# FliegerPCB10.net
KiCad netlist of a schematic drawn in EAGLE
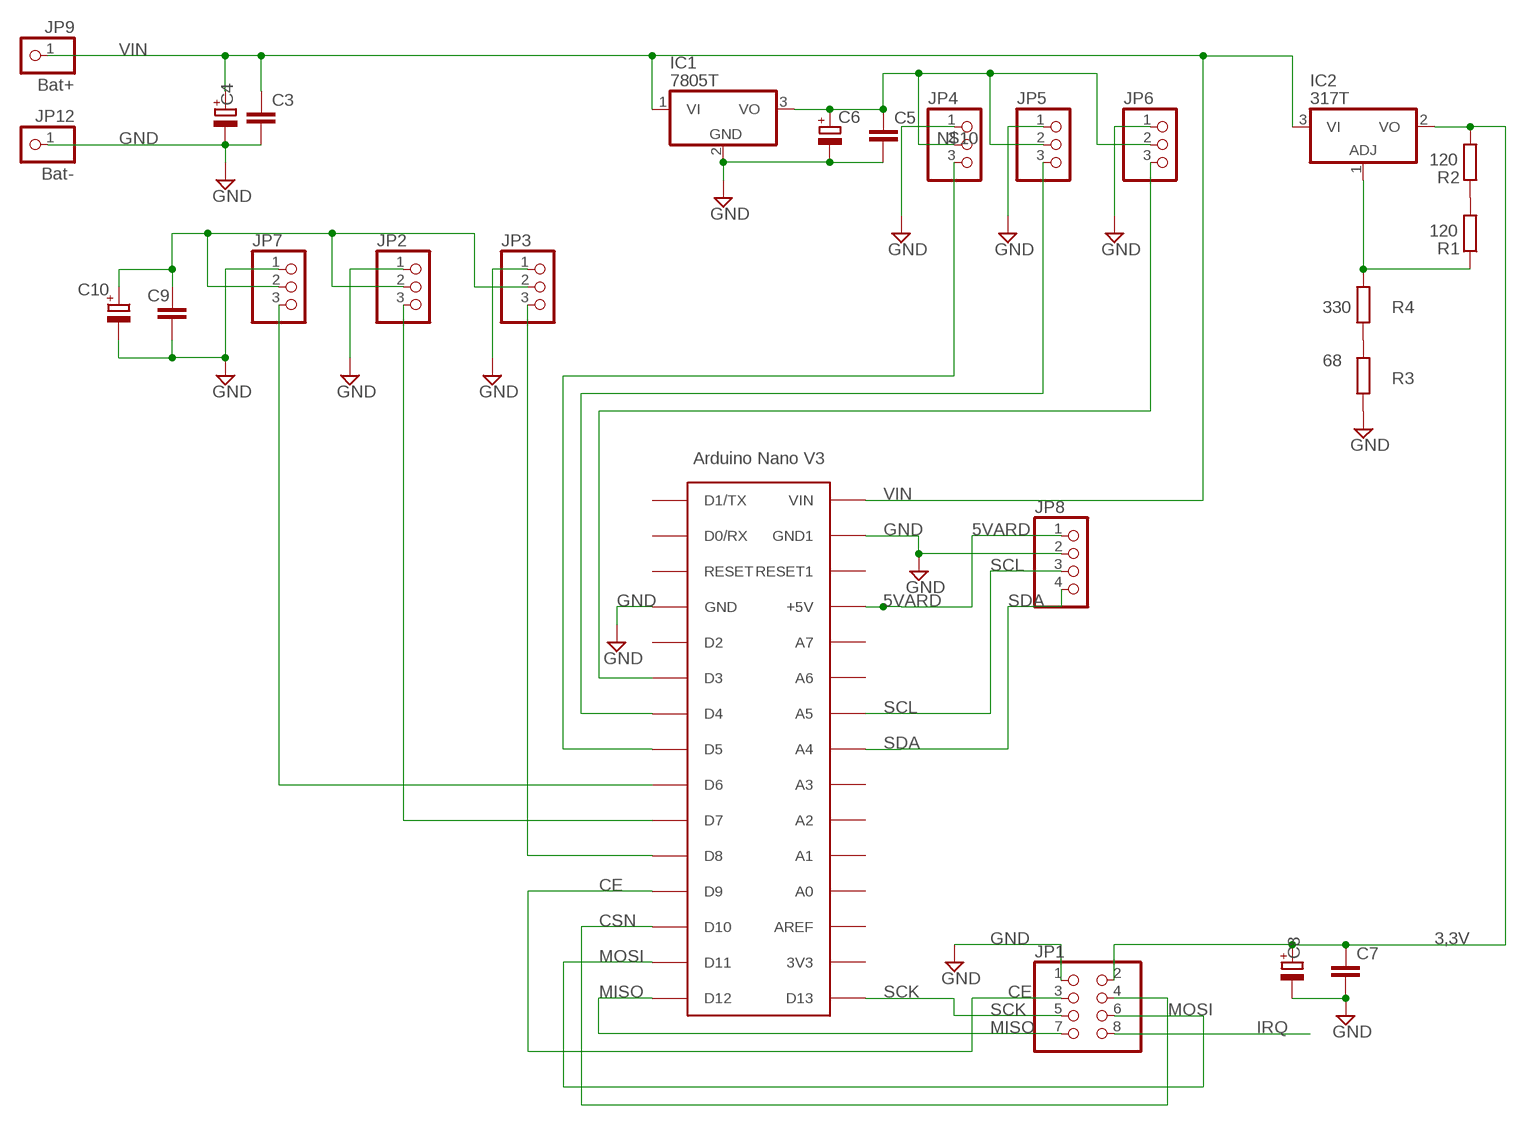
[diagram p0: schematic, sheet 1]

(export (version "E")
  (design (tool "Eeschema 10.0.6"))
  (components
    (comp (ref "C3")
      (value "C-EU050-024X044")
      (footprint "eagle-import:C050-024X044")
      (libsource (lib "eagle-import") (part "C-EU050-024X044"))
    )
    (comp (ref "C4")
      (value "CPOL-EUE5-10.5")
      (footprint "eagle-import:E5-10,5")
      (libsource (lib "eagle-import") (part "CPOL-EUE5-10.5"))
    )
    (comp (ref "C5")
      (value "C-EU050-024X044")
      (footprint "eagle-import:C050-024X044")
      (libsource (lib "eagle-import") (part "C-EU050-024X044"))
    )
    (comp (ref "C6")
      (value "CPOL-EUE5-10.5")
      (footprint "eagle-import:E5-10,5")
      (libsource (lib "eagle-import") (part "CPOL-EUE5-10.5"))
    )
    (comp (ref "C7")
      (value "C-EU050-024X044")
      (footprint "eagle-import:C050-024X044")
      (libsource (lib "eagle-import") (part "C-EU050-024X044"))
    )
    (comp (ref "C8")
      (value "CPOL-EUE3.5-8")
      (footprint "eagle-import:E3,5-8")
      (libsource (lib "eagle-import") (part "CPOL-EUE3.5-8"))
    )
    (comp (ref "C9")
      (value "C-EU050-024X044")
      (footprint "eagle-import:C050-024X044")
      (libsource (lib "eagle-import") (part "C-EU050-024X044"))
    )
    (comp (ref "C10")
      (value "CPOL-EUE5-10.5")
      (footprint "eagle-import:E5-10,5")
      (libsource (lib "eagle-import") (part "CPOL-EUE5-10.5"))
    )
    (comp (ref "IC1")
      (value "7805T")
      (footprint "eagle-import:TO220H")
      (libsource (lib "eagle-import") (part "78T05"))
    )
    (comp (ref "IC2")
      (value "317T")
      (footprint "eagle-import:TO220H")
      (libsource (lib "eagle-import") (part "317T"))
    )
    (comp (ref "JP1")
      (value "PINHD-2X4")
      (footprint "eagle-import:2X04")
      (libsource (lib "eagle-import") (part "PINHD-2X4"))
    )
    (comp (ref "JP2")
      (value "PINHD-1X3")
      (footprint "eagle-import:1X03")
      (libsource (lib "eagle-import") (part "PINHD-1X3"))
    )
    (comp (ref "JP3")
      (value "PINHD-1X3")
      (footprint "eagle-import:1X03")
      (libsource (lib "eagle-import") (part "PINHD-1X3"))
    )
    (comp (ref "JP4")
      (value "PINHD-1X3")
      (footprint "eagle-import:1X03")
      (libsource (lib "eagle-import") (part "PINHD-1X3"))
    )
    (comp (ref "JP5")
      (value "PINHD-1X3")
      (footprint "eagle-import:1X03")
      (libsource (lib "eagle-import") (part "PINHD-1X3"))
    )
    (comp (ref "JP6")
      (value "PINHD-1X3")
      (footprint "eagle-import:1X03")
      (libsource (lib "eagle-import") (part "PINHD-1X3"))
    )
    (comp (ref "JP7")
      (value "PINHD-1X3")
      (footprint "eagle-import:1X03")
      (libsource (lib "eagle-import") (part "PINHD-1X3"))
    )
    (comp (ref "JP8")
      (value "PINHD-1X4")
      (footprint "eagle-import:1X04")
      (libsource (lib "eagle-import") (part "PINHD-1X4"))
    )
    (comp (ref "JP9")
      (value "Bat+")
      (footprint "eagle-import:1X01")
      (libsource (lib "eagle-import") (part "PINHD-1X1"))
    )
    (comp (ref "JP12")
      (value "Bat-")
      (footprint "eagle-import:1X01")
      (libsource (lib "eagle-import") (part "PINHD-1X1"))
    )
    (comp (ref "R1")
      (value "120")
      (footprint "eagle-import:0207_10")
      (libsource (lib "eagle-import") (part "R-EU_0207/10"))
    )
    (comp (ref "R2")
      (value "120")
      (footprint "eagle-import:0207_10")
      (libsource (lib "eagle-import") (part "R-EU_0207/10"))
    )
    (comp (ref "R3")
      (value "68")
      (footprint "eagle-import:0207_10")
      (libsource (lib "eagle-import") (part "R-EU_0207/10"))
    )
    (comp (ref "R4")
      (value "330")
      (footprint "eagle-import:0207_10")
      (libsource (lib "eagle-import") (part "R-EU_0207/10"))
    )
    (comp (ref "U$1")
      (value "ARDUINONANO")
      (footprint "eagle-import:PDIP-32")
      (libsource (lib "eagle-import") (part "ARDUINONANO"))
    )
  )
  (nets
    (net (code "1") (name "/3,3V") (class "Default")
      (node (ref "C7") (pin "1") (pinfunction "1_1") (pintype "passive"))
      (node (ref "C8") (pin "+") (pinfunction "+_+") (pintype "passive"))
      (node (ref "IC2") (pin "2") (pinfunction "VO_2") (pintype "passive"))
      (node (ref "JP1") (pin "2") (pinfunction "2_2") (pintype "passive"))
      (node (ref "R2") (pin "2") (pinfunction "2_2") (pintype "passive"))
    )
    (net (code "2") (name "/5VARD") (class "Default")
      (node (ref "JP8") (pin "1") (pinfunction "1_1") (pintype "passive"))
      (node (ref "U$1") (pin "+5V") (pinfunction "+5V_+5V") (pintype "bidirectional"))
    )
    (net (code "3") (name "/CE") (class "Default")
      (node (ref "JP1") (pin "3") (pinfunction "3_3") (pintype "passive"))
      (node (ref "U$1") (pin "D9") (pinfunction "D9_D9") (pintype "bidirectional"))
    )
    (net (code "4") (name "/CSN") (class "Default")
      (node (ref "JP1") (pin "4") (pinfunction "4_4") (pintype "passive"))
      (node (ref "U$1") (pin "D10") (pinfunction "D10_D10") (pintype "bidirectional"))
    )
    (net (code "5") (name "/IRQ") (class "Default")
      (node (ref "JP1") (pin "8") (pinfunction "8_8") (pintype "passive"))
    )
    (net (code "6") (name "/MISO") (class "Default")
      (node (ref "JP1") (pin "7") (pinfunction "7_7") (pintype "passive"))
      (node (ref "U$1") (pin "D12") (pinfunction "D12_D12") (pintype "bidirectional"))
    )
    (net (code "7") (name "/MOSI") (class "Default")
      (node (ref "JP1") (pin "6") (pinfunction "6_6") (pintype "passive"))
      (node (ref "U$1") (pin "D11") (pinfunction "D11_D11") (pintype "bidirectional"))
    )
    (net (code "8") (name "/N$10") (class "Default")
      (node (ref "C5") (pin "1") (pinfunction "1_1") (pintype "passive"))
      (node (ref "C6") (pin "+") (pinfunction "+_+") (pintype "passive"))
      (node (ref "IC1") (pin "3") (pinfunction "VO_3") (pintype "passive"))
      (node (ref "JP4") (pin "2") (pinfunction "2_2") (pintype "passive"))
      (node (ref "JP5") (pin "2") (pinfunction "2_2") (pintype "passive"))
      (node (ref "JP6") (pin "2") (pinfunction "2_2") (pintype "passive"))
    )
    (net (code "9") (name "/SCK") (class "Default")
      (node (ref "JP1") (pin "5") (pinfunction "5_5") (pintype "passive"))
      (node (ref "U$1") (pin "D13") (pinfunction "D13_D13") (pintype "bidirectional"))
    )
    (net (code "10") (name "/SCL") (class "Default")
      (node (ref "JP8") (pin "3") (pinfunction "3_3") (pintype "passive"))
      (node (ref "U$1") (pin "A2") (pinfunction "A5_A2") (pintype "bidirectional"))
    )
    (net (code "11") (name "/SDA") (class "Default")
      (node (ref "JP8") (pin "4") (pinfunction "4_4") (pintype "passive"))
      (node (ref "U$1") (pin "A3") (pinfunction "A4_A3") (pintype "bidirectional"))
    )
    (net (code "12") (name "/VIN") (class "Default")
      (node (ref "C3") (pin "1") (pinfunction "1_1") (pintype "passive"))
      (node (ref "C4") (pin "+") (pinfunction "+_+") (pintype "passive"))
      (node (ref "IC1") (pin "1") (pinfunction "VI_1") (pintype "input"))
      (node (ref "IC2") (pin "3") (pinfunction "VI_3") (pintype "input"))
      (node (ref "JP9") (pin "1") (pinfunction "1_1") (pintype "passive"))
      (node (ref "U$1") (pin "VIN") (pinfunction "VIN_VIN") (pintype "bidirectional"))
    )
    (net (code "13") (name "GND") (class "Default")
      (node (ref "C10") (pin "-") (pinfunction "-_-") (pintype "passive"))
      (node (ref "C3") (pin "2") (pinfunction "2_2") (pintype "passive"))
      (node (ref "C4") (pin "-") (pinfunction "-_-") (pintype "passive"))
      (node (ref "C5") (pin "2") (pinfunction "2_2") (pintype "passive"))
      (node (ref "C6") (pin "-") (pinfunction "-_-") (pintype "passive"))
      (node (ref "C7") (pin "2") (pinfunction "2_2") (pintype "passive"))
      (node (ref "C8") (pin "-") (pinfunction "-_-") (pintype "passive"))
      (node (ref "C9") (pin "2") (pinfunction "2_2") (pintype "passive"))
      (node (ref "IC1") (pin "2") (pinfunction "GND_2") (pintype "passive"))
      (node (ref "JP1") (pin "1") (pinfunction "1_1") (pintype "passive"))
      (node (ref "JP12") (pin "1") (pinfunction "1_1") (pintype "passive"))
      (node (ref "JP2") (pin "1") (pinfunction "1_1") (pintype "passive"))
      (node (ref "JP3") (pin "1") (pinfunction "1_1") (pintype "passive"))
      (node (ref "JP4") (pin "1") (pinfunction "1_1") (pintype "passive"))
      (node (ref "JP5") (pin "1") (pinfunction "1_1") (pintype "passive"))
      (node (ref "JP6") (pin "1") (pinfunction "1_1") (pintype "passive"))
      (node (ref "JP7") (pin "1") (pinfunction "1_1") (pintype "passive"))
      (node (ref "JP8") (pin "2") (pinfunction "2_2") (pintype "passive"))
      (node (ref "R3") (pin "2") (pinfunction "2_2") (pintype "passive"))
      (node (ref "U$1") (pin "GND") (pinfunction "GND_GND") (pintype "bidirectional"))
      (node (ref "U$1") (pin "GND1") (pinfunction "GND1_GND1") (pintype "bidirectional"))
    )
    (net (code "14") (name "Net-(C10-Pad+)") (class "Default")
      (node (ref "C10") (pin "+") (pinfunction "+_+") (pintype "passive"))
      (node (ref "C9") (pin "1") (pinfunction "1_1") (pintype "passive"))
      (node (ref "JP2") (pin "2") (pinfunction "2_2") (pintype "passive"))
      (node (ref "JP3") (pin "2") (pinfunction "2_2") (pintype "passive"))
      (node (ref "JP7") (pin "2") (pinfunction "2_2") (pintype "passive"))
    )
    (net (code "15") (name "Net-(IC2-ADJ)") (class "Default")
      (node (ref "IC2") (pin "1") (pinfunction "ADJ_1") (pintype "input"))
      (node (ref "R1") (pin "1") (pinfunction "1_1") (pintype "passive"))
      (node (ref "R4") (pin "1") (pinfunction "1_1") (pintype "passive"))
    )
    (net (code "16") (name "Net-(JP2-Pad3)") (class "Default")
      (node (ref "JP2") (pin "3") (pinfunction "3_3") (pintype "passive"))
      (node (ref "U$1") (pin "D7") (pinfunction "D7_D7") (pintype "bidirectional"))
    )
    (net (code "17") (name "Net-(JP3-Pad3)") (class "Default")
      (node (ref "JP3") (pin "3") (pinfunction "3_3") (pintype "passive"))
      (node (ref "U$1") (pin "D8") (pinfunction "D8_D8") (pintype "bidirectional"))
    )
    (net (code "18") (name "Net-(JP4-Pad3)") (class "Default")
      (node (ref "JP4") (pin "3") (pinfunction "3_3") (pintype "passive"))
      (node (ref "U$1") (pin "D5") (pinfunction "D5_D5") (pintype "bidirectional"))
    )
    (net (code "19") (name "Net-(JP5-Pad3)") (class "Default")
      (node (ref "JP5") (pin "3") (pinfunction "3_3") (pintype "passive"))
      (node (ref "U$1") (pin "D4") (pinfunction "D4_D4") (pintype "bidirectional"))
    )
    (net (code "20") (name "Net-(JP6-Pad3)") (class "Default")
      (node (ref "JP6") (pin "3") (pinfunction "3_3") (pintype "passive"))
      (node (ref "U$1") (pin "D3") (pinfunction "D3_D3") (pintype "bidirectional"))
    )
    (net (code "21") (name "Net-(JP7-Pad3)") (class "Default")
      (node (ref "JP7") (pin "3") (pinfunction "3_3") (pintype "passive"))
      (node (ref "U$1") (pin "D6") (pinfunction "D6_D6") (pintype "bidirectional"))
    )
    (net (code "22") (name "Net-(R1-Pad2)") (class "Default")
      (node (ref "R1") (pin "2") (pinfunction "2_2") (pintype "passive"))
      (node (ref "R2") (pin "1") (pinfunction "1_1") (pintype "passive"))
    )
    (net (code "23") (name "Net-(R3-Pad1)") (class "Default")
      (node (ref "R3") (pin "1") (pinfunction "1_1") (pintype "passive"))
      (node (ref "R4") (pin "2") (pinfunction "2_2") (pintype "passive"))
    )
    (net (code "24") (name "unconnected-(U$1-A0-PadA7)") (class "Default")
      (node (ref "U$1") (pin "A7") (pinfunction "A0_A7") (pintype "bidirectional"))
    )
    (net (code "25") (name "unconnected-(U$1-A1-PadA6)") (class "Default")
      (node (ref "U$1") (pin "A6") (pinfunction "A1_A6") (pintype "bidirectional"))
    )
    (net (code "26") (name "unconnected-(U$1-A2-PadA5)") (class "Default")
      (node (ref "U$1") (pin "A5") (pinfunction "A2_A5") (pintype "bidirectional"))
    )
    (net (code "27") (name "unconnected-(U$1-A3-PadA4)") (class "Default")
      (node (ref "U$1") (pin "A4") (pinfunction "A3_A4") (pintype "bidirectional"))
    )
    (net (code "28") (name "unconnected-(U$1-A6-PadA1)") (class "Default")
      (node (ref "U$1") (pin "A1") (pinfunction "A6_A1") (pintype "bidirectional"))
    )
    (net (code "29") (name "unconnected-(U$1-A7-PadA0)") (class "Default")
      (node (ref "U$1") (pin "A0") (pinfunction "A7_A0") (pintype "bidirectional"))
    )
    (net (code "30") (name "unconnected-(U$1-Pad3V3)") (class "Default")
      (node (ref "U$1") (pin "3V3") (pinfunction "3V3_3V3") (pintype "bidirectional"))
    )
    (net (code "31") (name "unconnected-(U$1-PadAREF)") (class "Default")
      (node (ref "U$1") (pin "AREF") (pinfunction "AREF_AREF") (pintype "bidirectional"))
    )
    (net (code "32") (name "unconnected-(U$1-PadD0{slash}RX)") (class "Default")
      (node (ref "U$1") (pin "D0/RX") (pinfunction "D0/RX_D0/RX") (pintype "bidirectional"))
    )
    (net (code "33") (name "unconnected-(U$1-PadD1{slash}TX)") (class "Default")
      (node (ref "U$1") (pin "D1/TX") (pinfunction "D1/TX_D1/TX") (pintype "bidirectional"))
    )
    (net (code "34") (name "unconnected-(U$1-PadD2)") (class "Default")
      (node (ref "U$1") (pin "D2") (pinfunction "D2_D2") (pintype "bidirectional"))
    )
    (net (code "35") (name "unconnected-(U$1-PadRESET)") (class "Default")
      (node (ref "U$1") (pin "RESET") (pinfunction "RESET_RESET") (pintype "bidirectional"))
    )
    (net (code "36") (name "unconnected-(U$1-PadRESET1)") (class "Default")
      (node (ref "U$1") (pin "RESET1") (pinfunction "RESET1_RESET1") (pintype "bidirectional"))
    )
  )
)
